# IMD_project.net
KiCad netlist of a schematic drawn in Altium Designer
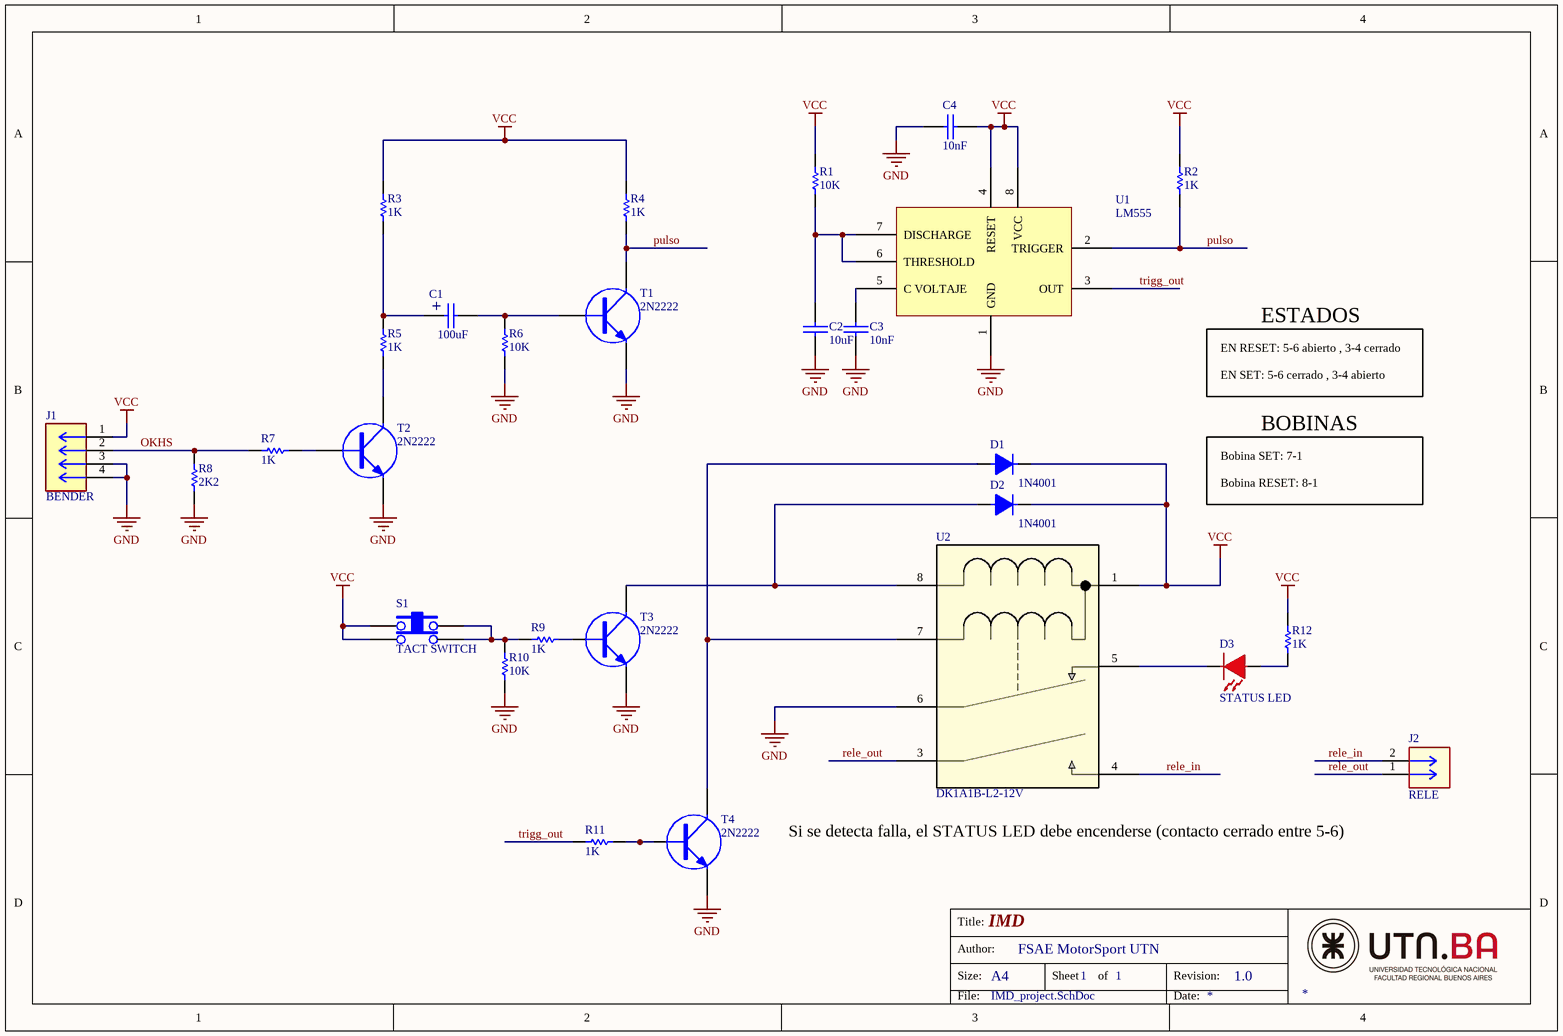
[diagram p0: IMD_project.SchDoc]

(export (version "E")
  (design (tool "Eeschema 10.0.6"))
  (components
    (comp (ref "C1")
      (value "100uF")
      (footprint "CAP300RP")
      (libsource (lib "imd_components") (part "CAPPOL"))
    )
    (comp (ref "C2") (value "10uF") (footprint "CAP200") (libsource (lib "imd_components") (part "CAP")))
    (comp (ref "C3") (value "10nF") (footprint "CAP200") (libsource (lib "imd_components") (part "CAP")))
    (comp (ref "C4") (value "10nF") (footprint "CAP200") (libsource (lib "imd_components") (part "CAP")))
    (comp (ref "D1")
      (value "1N4001")
      (footprint "DO41")
      (description "Diodo")
      (libsource (lib "imd_components") (part "1N4001"))
    )
    (comp (ref "D2")
      (value "1N4001")
      (footprint "DO41")
      (description "Diodo")
      (libsource (lib "imd_components") (part "1N4001"))
    )
    (comp (ref "D3")
      (value "STATUS LED")
      (footprint "LED 3 - Red")
      (description "LED ROJO")
      (libsource (lib "imd_components") (part "LED ROJO"))
    )
    (comp (ref "J1")
      (value "BENDER")
      (footprint "CONN_SD-44067-001_04_MOL")
      (description "Molex mini 40 de 4 pines (347920040)")
      (fields (field (name "MP") "347920040"))
      (libsource (lib "imd_components") (part "MolexMini 4"))
    )
    (comp (ref "J2")
      (value "RELE")
      (footprint "CONN_SD-44067-001_02_MOL")
      (fields
        (field (name "MANUFACTURER_PART_NUMBER") "440670201")
        (field (name "COPYRIGHT") "Copyright (C) 2025 Ultra Librarian. All rights reserved.")
      )
      (libsource (lib "imd_components") (part "MolexMini 2"))
    )
    (comp (ref "R1") (value "10K") (footprint "RES400") (libsource (lib "imd_components") (part "RES")))
    (comp (ref "R2") (value "1K") (footprint "RES400") (libsource (lib "imd_components") (part "RES")))
    (comp (ref "R3") (value "1K") (footprint "RES400") (libsource (lib "imd_components") (part "RES")))
    (comp (ref "R4") (value "1K") (footprint "RES400") (libsource (lib "imd_components") (part "RES")))
    (comp (ref "R5") (value "1K") (footprint "RES400") (libsource (lib "imd_components") (part "RES")))
    (comp (ref "R6") (value "10K") (footprint "RES400") (libsource (lib "imd_components") (part "RES")))
    (comp (ref "R7") (value "1K") (footprint "RES400") (libsource (lib "imd_components") (part "RES")))
    (comp (ref "R8") (value "2K2") (footprint "RES400") (libsource (lib "imd_components") (part "RES")))
    (comp (ref "R9") (value "1K") (footprint "RES400") (libsource (lib "imd_components") (part "RES")))
    (comp (ref "R10") (value "10K") (footprint "RES400") (libsource (lib "imd_components") (part "RES")))
    (comp (ref "R11") (value "1K") (footprint "RES400") (libsource (lib "imd_components") (part "RES")))
    (comp (ref "R12") (value "1K") (footprint "RES400") (libsource (lib "imd_components") (part "RES")))
    (comp (ref "S1")
      (value "TACT SWITCH")
      (footprint "TACTSWITCH")
      (libsource (lib "imd_components") (part "TACT SWITCH"))
    )
    (comp (ref "T1")
      (value "2N2222")
      (footprint "TO-18")
      (libsource (lib "imd_components") (part "TRANSISTOR NPN"))
    )
    (comp (ref "T2")
      (value "2N2222")
      (footprint "TO-18")
      (libsource (lib "imd_components") (part "TRANSISTOR NPN"))
    )
    (comp (ref "T3")
      (value "2N2222")
      (footprint "TO-18")
      (libsource (lib "imd_components") (part "TRANSISTOR NPN"))
    )
    (comp (ref "T4")
      (value "2N2222")
      (footprint "TO-18")
      (libsource (lib "imd_components") (part "TRANSISTOR NPN"))
    )
    (comp (ref "U1")
      (value "LM555")
      (footprint "DIP8")
      (description "Timer")
      (libsource (lib "imd_components") (part "LM555"))
    )
    (comp (ref "U2")
      (value "DK1A1B-L2-12V")
      (footprint "RELAY_DK2A_L2_PAN")
      (description "Description")
      (fields (field (name "COPYRIGHT") "Copyright (C) 2026 Ultra Librarian. All rights reserved."))
      (libsource (lib "imd_components") (part "DK1A1B-L2-12V"))
    )
  )
  (nets
    (net (code "1") (name "/OKHS") (class "Default")
      (node (ref "J1") (pin "2") (pinfunction "2_2") (pintype "passive"))
      (node (ref "R7") (pin "2") (pinfunction "2_2") (pintype "passive"))
      (node (ref "R8") (pin "2") (pinfunction "2_2") (pintype "passive"))
    )
    (net (code "2") (name "/pulso") (class "Default")
      (node (ref "R2") (pin "1") (pinfunction "1_1") (pintype "passive"))
      (node (ref "R4") (pin "1") (pinfunction "1_1") (pintype "passive"))
      (node (ref "T1") (pin "2") (pinfunction "C_2") (pintype "passive"))
      (node (ref "U1") (pin "2") (pinfunction "TRIGGER_2") (pintype "passive"))
    )
    (net (code "3") (name "/rele_in") (class "Default")
      (node (ref "J2") (pin "2") (pinfunction "2_2") (pintype "passive"))
      (node (ref "U2") (pin "4") (pinfunction "3_4") (pintype "passive"))
    )
    (net (code "4") (name "/rele_out") (class "Default")
      (node (ref "J2") (pin "1") (pinfunction "1_1") (pintype "passive"))
      (node (ref "U2") (pin "3") (pinfunction "6_3") (pintype "passive"))
    )
    (net (code "5") (name "/trigg_out") (class "Default")
      (node (ref "R11") (pin "2") (pinfunction "2_2") (pintype "passive"))
      (node (ref "U1") (pin "3") (pinfunction "OUT_3") (pintype "passive"))
    )
    (net (code "6") (name "GND") (class "Default")
      (node (ref "C2") (pin "2") (pinfunction "2_2") (pintype "passive"))
      (node (ref "C3") (pin "2") (pinfunction "2_2") (pintype "passive"))
      (node (ref "C4") (pin "2") (pinfunction "2_2") (pintype "passive"))
      (node (ref "J1") (pin "3") (pinfunction "3_3") (pintype "passive"))
      (node (ref "J1") (pin "4") (pinfunction "4_4") (pintype "passive"))
      (node (ref "R10") (pin "2") (pinfunction "2_2") (pintype "passive"))
      (node (ref "R6") (pin "1") (pinfunction "1_1") (pintype "passive"))
      (node (ref "R8") (pin "1") (pinfunction "1_1") (pintype "passive"))
      (node (ref "T1") (pin "3") (pinfunction "E_3") (pintype "passive"))
      (node (ref "T2") (pin "3") (pinfunction "E_3") (pintype "passive"))
      (node (ref "T3") (pin "3") (pinfunction "E_3") (pintype "passive"))
      (node (ref "T4") (pin "3") (pinfunction "E_3") (pintype "passive"))
      (node (ref "U1") (pin "1") (pinfunction "GND_1") (pintype "passive"))
      (node (ref "U2") (pin "6") (pinfunction "7_6") (pintype "passive"))
    )
    (net (code "7") (name "Net-(C1-Pad1)") (class "Default")
      (node (ref "C1") (pin "1") (pinfunction "1_1") (pintype "passive"))
      (node (ref "R3") (pin "1") (pinfunction "1_1") (pintype "passive"))
      (node (ref "R5") (pin "2") (pinfunction "2_2") (pintype "passive"))
    )
    (net (code "8") (name "Net-(D3-Pad1)") (class "Default")
      (node (ref "D3") (pin "1") (pinfunction "1_1") (pintype "passive"))
      (node (ref "R12") (pin "1") (pinfunction "1_1") (pintype "passive"))
    )
    (net (code "9") (name "Net-(D3-Pad2)") (class "Default")
      (node (ref "D3") (pin "2") (pinfunction "2_2") (pintype "passive"))
      (node (ref "U2") (pin "5") (pinfunction "5_5") (pintype "passive"))
    )
    (net (code "10") (name "Net-(R10-Pad1)") (class "Default")
      (node (ref "R10") (pin "1") (pinfunction "1_1") (pintype "passive"))
      (node (ref "R9") (pin "2") (pinfunction "2_2") (pintype "passive"))
      (node (ref "S1") (pin "3") (pinfunction "3_3") (pintype "passive"))
      (node (ref "S1") (pin "4") (pinfunction "4_4") (pintype "passive"))
    )
    (net (code "11") (name "Net-(T1-B)") (class "Default")
      (node (ref "C1") (pin "2") (pinfunction "2_2") (pintype "passive"))
      (node (ref "R6") (pin "2") (pinfunction "2_2") (pintype "passive"))
      (node (ref "T1") (pin "1") (pinfunction "B_1") (pintype "passive"))
    )
    (net (code "12") (name "Net-(T2-B)") (class "Default")
      (node (ref "R7") (pin "1") (pinfunction "1_1") (pintype "passive"))
      (node (ref "T2") (pin "1") (pinfunction "B_1") (pintype "passive"))
    )
    (net (code "13") (name "Net-(T2-C)") (class "Default")
      (node (ref "R5") (pin "1") (pinfunction "1_1") (pintype "passive"))
      (node (ref "T2") (pin "2") (pinfunction "C_2") (pintype "passive"))
    )
    (net (code "14") (name "Net-(T3-B)") (class "Default")
      (node (ref "R9") (pin "1") (pinfunction "1_1") (pintype "passive"))
      (node (ref "T3") (pin "1") (pinfunction "B_1") (pintype "passive"))
    )
    (net (code "15") (name "Net-(T3-C)") (class "Default")
      (node (ref "D2") (pin "1") (pinfunction "1_1") (pintype "passive"))
      (node (ref "T3") (pin "2") (pinfunction "C_2") (pintype "passive"))
      (node (ref "U2") (pin "8") (pinfunction "1_8") (pintype "passive"))
    )
    (net (code "16") (name "Net-(T4-B)") (class "Default")
      (node (ref "R11") (pin "1") (pinfunction "1_1") (pintype "passive"))
      (node (ref "T4") (pin "1") (pinfunction "B_1") (pintype "passive"))
    )
    (net (code "17") (name "Net-(T4-C)") (class "Default")
      (node (ref "D1") (pin "1") (pinfunction "1_1") (pintype "passive"))
      (node (ref "T4") (pin "2") (pinfunction "C_2") (pintype "passive"))
      (node (ref "U2") (pin "7") (pinfunction "2_7") (pintype "passive"))
    )
    (net (code "18") (name "Net-(U1-C_VOLTAJE)") (class "Default")
      (node (ref "C3") (pin "1") (pinfunction "1_1") (pintype "passive"))
      (node (ref "U1") (pin "5") (pinfunction "C_VOLTAJE_5") (pintype "passive"))
    )
    (net (code "19") (name "Net-(U1-DISCHARGE)") (class "Default")
      (node (ref "C2") (pin "1") (pinfunction "1_1") (pintype "passive"))
      (node (ref "R1") (pin "1") (pinfunction "1_1") (pintype "passive"))
      (node (ref "U1") (pin "6") (pinfunction "THRESHOLD_6") (pintype "passive"))
      (node (ref "U1") (pin "7") (pinfunction "DISCHARGE_7") (pintype "passive"))
    )
    (net (code "20") (name "VCC") (class "Default")
      (node (ref "C4") (pin "1") (pinfunction "1_1") (pintype "passive"))
      (node (ref "D1") (pin "2") (pinfunction "2_2") (pintype "passive"))
      (node (ref "D2") (pin "2") (pinfunction "2_2") (pintype "passive"))
      (node (ref "J1") (pin "1") (pinfunction "1_1") (pintype "passive"))
      (node (ref "R1") (pin "2") (pinfunction "2_2") (pintype "passive"))
      (node (ref "R12") (pin "2") (pinfunction "2_2") (pintype "passive"))
      (node (ref "R2") (pin "2") (pinfunction "2_2") (pintype "passive"))
      (node (ref "R3") (pin "2") (pinfunction "2_2") (pintype "passive"))
      (node (ref "R4") (pin "2") (pinfunction "2_2") (pintype "passive"))
      (node (ref "S1") (pin "1") (pinfunction "1_1") (pintype "passive"))
      (node (ref "S1") (pin "2") (pinfunction "2_2") (pintype "passive"))
      (node (ref "U1") (pin "4") (pinfunction "RESET_4") (pintype "passive"))
      (node (ref "U1") (pin "8") (pinfunction "VCC_8") (pintype "passive"))
      (node (ref "U2") (pin "1") (pinfunction "4_1") (pintype "passive"))
    )
  )
)
